# Electrodos.net
KiCad netlist of a schematic drawn in Altium Designer
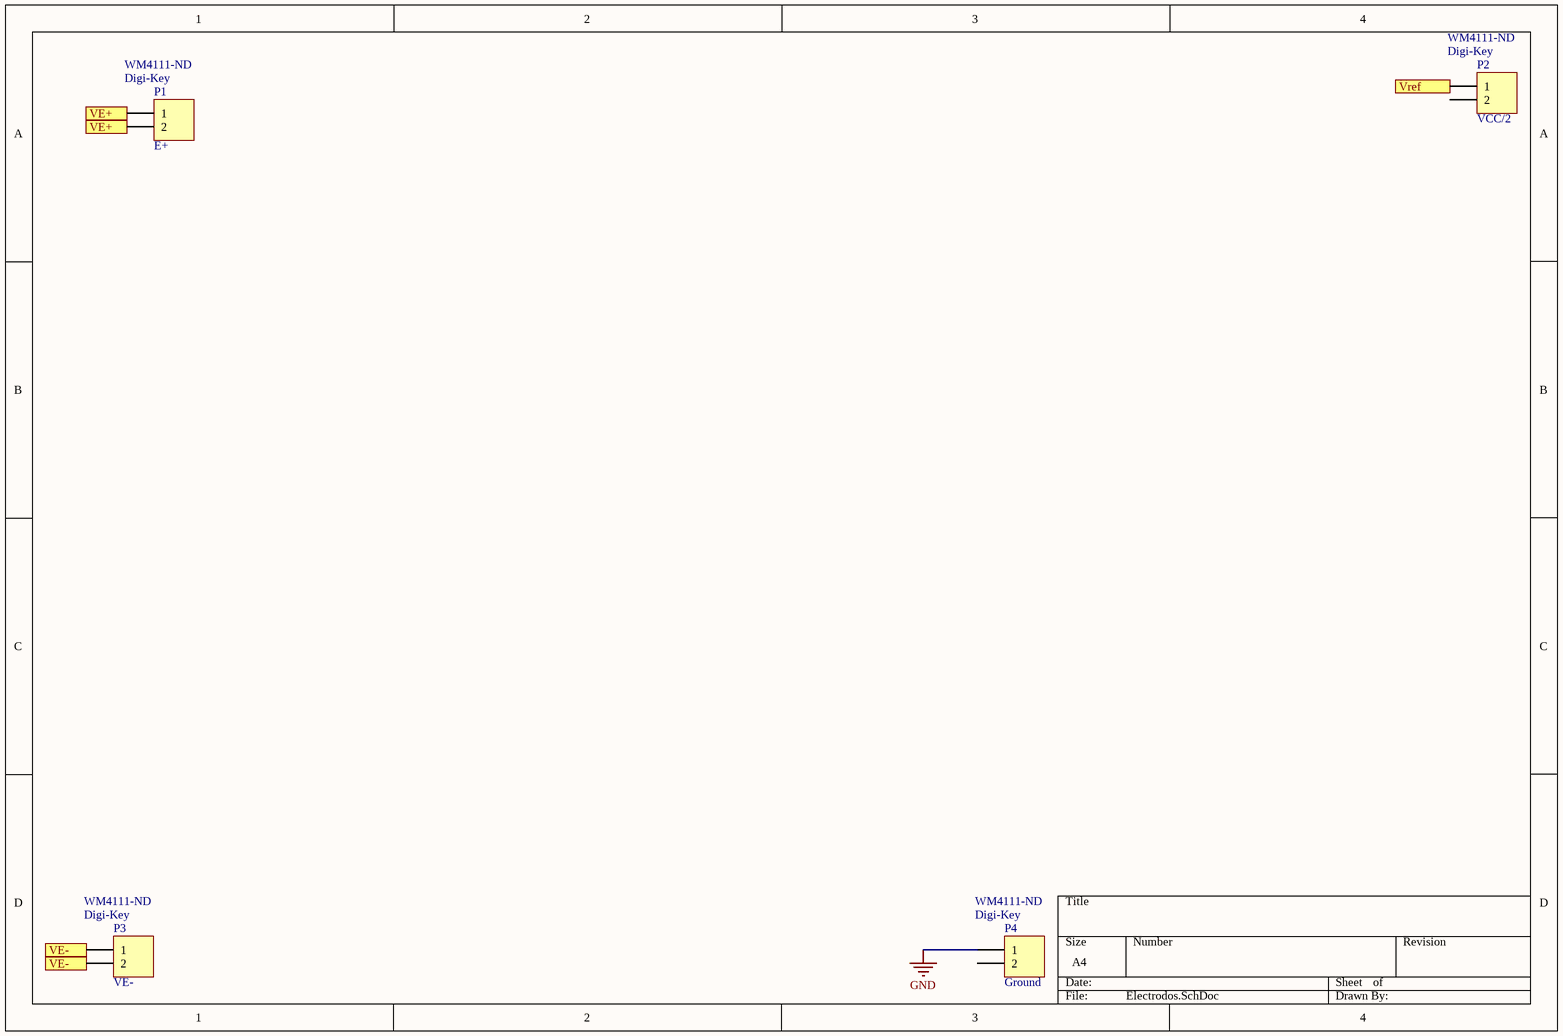
[diagram p0: Electrodos.SchDoc]

(export (version "E")
  (design (tool "Eeschema 10.0.6"))
  (components
    (comp (ref "P1")
      (value "E+")
      (footprint "HDR1X2")
      (description "Header, 2-Pin")
      (fields
        (field (name "SUPPLIER 1") "Digi-Key")
        (field (name "SUPPLIER PART NUMBER 1") "WM4111-ND")
        (field (name "PUBLISHER") "Altium Limited")
      )
      (libsource (lib "Miscellaneous Connectors") (part "Header 2"))
    )
    (comp (ref "P2")
      (value "VCC/2")
      (footprint "HDR1X2")
      (description "Header, 2-Pin")
      (fields
        (field (name "SUPPLIER 1") "Digi-Key")
        (field (name "SUPPLIER PART NUMBER 1") "WM4111-ND")
        (field (name "PUBLISHER") "Altium Limited")
      )
      (libsource (lib "Miscellaneous Connectors") (part "Header 2"))
    )
    (comp (ref "P3")
      (value "VE-")
      (footprint "HDR1X2")
      (description "Header, 2-Pin")
      (fields
        (field (name "SUPPLIER 1") "Digi-Key")
        (field (name "SUPPLIER PART NUMBER 1") "WM4111-ND")
        (field (name "PUBLISHER") "Altium Limited")
      )
      (libsource (lib "Miscellaneous Connectors") (part "Header 2"))
    )
    (comp (ref "P4")
      (value "Ground")
      (footprint "HDR1X2")
      (description "Header, 2-Pin")
      (fields
        (field (name "SUPPLIER 1") "Digi-Key")
        (field (name "SUPPLIER PART NUMBER 1") "WM4111-ND")
        (field (name "PUBLISHER") "Altium Limited")
      )
      (libsource (lib "Miscellaneous Connectors") (part "Header 2"))
    )
  )
  (nets
    (net (code "1") (name "/VE+") (class "Default")
      (node (ref "P1") (pin "1") (pinfunction "1_1") (pintype "passive"))
      (node (ref "P1") (pin "2") (pinfunction "2_2") (pintype "passive"))
    )
    (net (code "2") (name "/VE-") (class "Default")
      (node (ref "P3") (pin "1") (pinfunction "1_1") (pintype "passive"))
      (node (ref "P3") (pin "2") (pinfunction "2_2") (pintype "passive"))
    )
    (net (code "3") (name "/Vref") (class "Default")
      (node (ref "P2") (pin "1") (pinfunction "1_1") (pintype "passive"))
    )
    (net (code "4") (name "GND") (class "Default")
      (node (ref "P4") (pin "1") (pinfunction "1_1") (pintype "passive"))
    )
    (net (code "5") (name "unconnected-(P2-Pad2)") (class "Default")
      (node (ref "P2") (pin "2") (pinfunction "2_2") (pintype "passive"))
    )
    (net (code "6") (name "unconnected-(P4-Pad2)") (class "Default")
      (node (ref "P4") (pin "2") (pinfunction "2_2") (pintype "passive"))
    )
  )
)
